# qi-charger.net
KiCad netlist of a schematic drawn in EAGLE
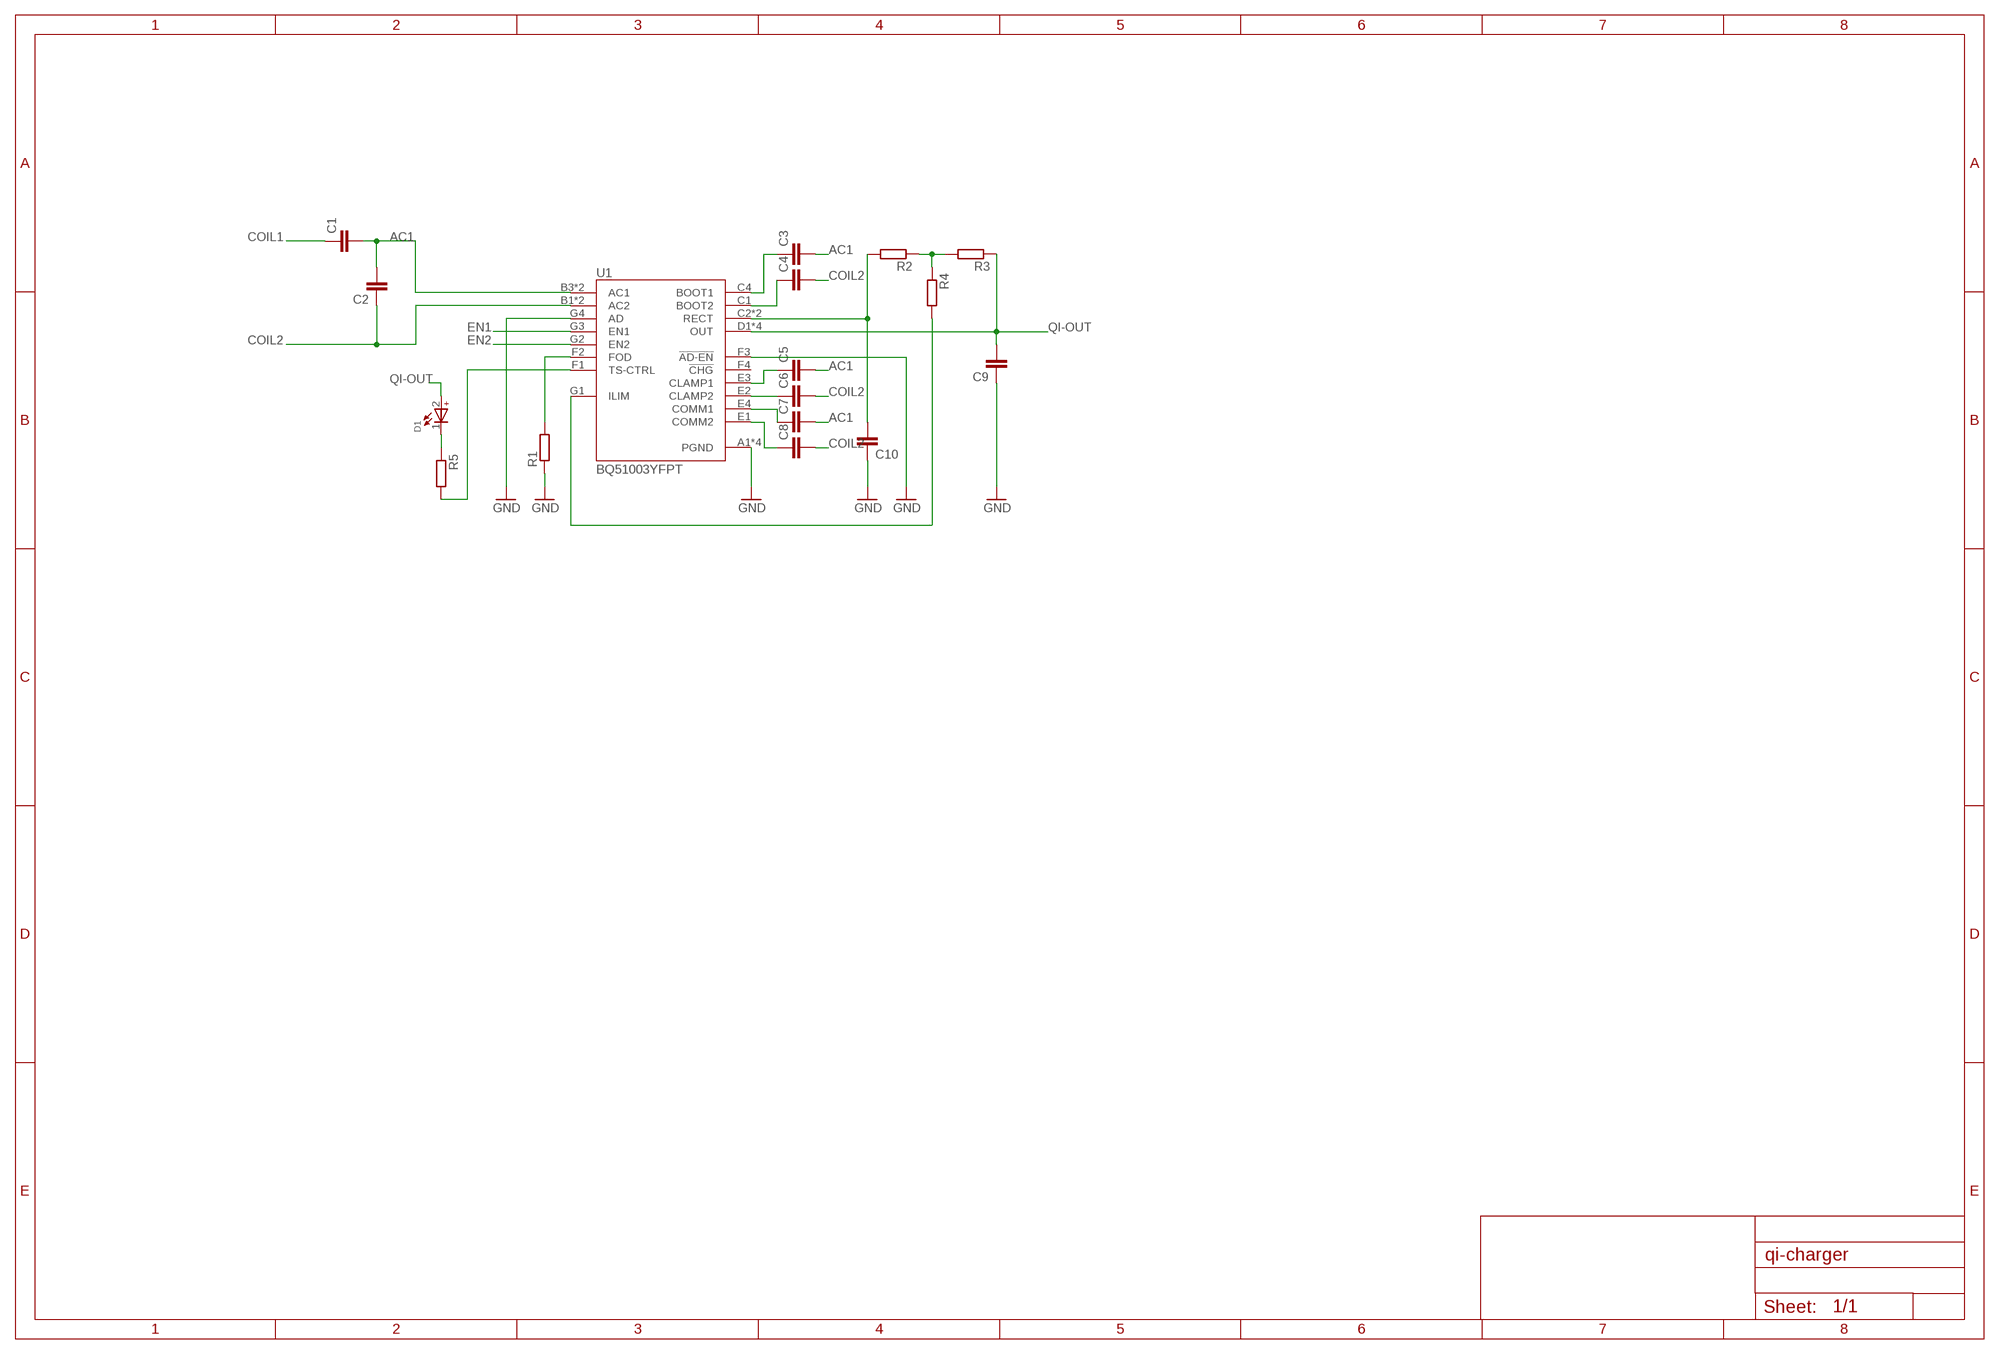
[diagram p0: schematic, sheet 1]

(export (version "E")
  (design (tool "Eeschema 10.0.6"))
  (components
    (comp (ref "C1")
      (value "C-EUC0805")
      (footprint "eagle-import:C0805")
      (libsource (lib "eagle-import") (part "C-EUC0805"))
    )
    (comp (ref "C2")
      (value "C-EUC0805")
      (footprint "eagle-import:C0805")
      (libsource (lib "eagle-import") (part "C-EUC0805"))
    )
    (comp (ref "C3")
      (value "C-EUC0805")
      (footprint "eagle-import:C0805")
      (libsource (lib "eagle-import") (part "C-EUC0805"))
    )
    (comp (ref "C4")
      (value "C-EUC0805")
      (footprint "eagle-import:C0805")
      (libsource (lib "eagle-import") (part "C-EUC0805"))
    )
    (comp (ref "C5")
      (value "C-EUC0805")
      (footprint "eagle-import:C0805")
      (libsource (lib "eagle-import") (part "C-EUC0805"))
    )
    (comp (ref "C6")
      (value "C-EUC0805")
      (footprint "eagle-import:C0805")
      (libsource (lib "eagle-import") (part "C-EUC0805"))
    )
    (comp (ref "C7")
      (value "C-EUC0805")
      (footprint "eagle-import:C0805")
      (libsource (lib "eagle-import") (part "C-EUC0805"))
    )
    (comp (ref "C8")
      (value "C-EUC0805")
      (footprint "eagle-import:C0805")
      (libsource (lib "eagle-import") (part "C-EUC0805"))
    )
    (comp (ref "C9")
      (value "C-EUC0805")
      (footprint "eagle-import:C0805")
      (libsource (lib "eagle-import") (part "C-EUC0805"))
    )
    (comp (ref "C10")
      (value "C-EUC0805")
      (footprint "eagle-import:C0805")
      (libsource (lib "eagle-import") (part "C-EUC0805"))
    )
    (comp (ref "D1")
      (value "WL-SMCW_0603_150060AS75000")
      (footprint "eagle-import:WL-SMCW_0603")
      (libsource (lib "eagle-import") (part "WL-SMCW_0603_150060AS75000"))
    )
    (comp (ref "R1")
      (value "R-EU_M0805")
      (footprint "eagle-import:M0805")
      (libsource (lib "eagle-import") (part "R-EU_M0805"))
    )
    (comp (ref "R2")
      (value "R-EU_M0805")
      (footprint "eagle-import:M0805")
      (libsource (lib "eagle-import") (part "R-EU_M0805"))
    )
    (comp (ref "R3")
      (value "R-EU_M0805")
      (footprint "eagle-import:M0805")
      (libsource (lib "eagle-import") (part "R-EU_M0805"))
    )
    (comp (ref "R4")
      (value "R-EU_M0805")
      (footprint "eagle-import:M0805")
      (libsource (lib "eagle-import") (part "R-EU_M0805"))
    )
    (comp (ref "R5")
      (value "R-EU_M0805")
      (footprint "eagle-import:M0805")
      (libsource (lib "eagle-import") (part "R-EU_M0805"))
    )
    (comp (ref "U1")
      (value "BQ51003YFPT")
      (footprint "eagle-import:BGA28N40P7X4_300X188X50N")
      (fields (field (name "MF") "Texas Instruments"))
      (libsource (lib "eagle-import") (part "BQ51003YFPT"))
    )
  )
  (nets
    (net (code "1") (name "/AC1") (class "Default")
      (node (ref "C1") (pin "2") (pinfunction "2_2") (pintype "passive"))
      (node (ref "C2") (pin "2") (pinfunction "2_2") (pintype "passive"))
      (node (ref "C3") (pin "2") (pinfunction "2_2") (pintype "passive"))
      (node (ref "C5") (pin "2") (pinfunction "2_2") (pintype "passive"))
      (node (ref "C7") (pin "2") (pinfunction "2_2") (pintype "passive"))
      (node (ref "U1") (pin "B3") (pinfunction "AC1_B3") (pintype "input"))
      (node (ref "U1") (pin "B4") (pinfunction "AC1_B4") (pintype "input"))
    )
    (net (code "2") (name "/COIL1") (class "Default")
      (node (ref "C1") (pin "1") (pinfunction "1_1") (pintype "passive"))
    )
    (net (code "3") (name "/COIL2") (class "Default")
      (node (ref "C2") (pin "1") (pinfunction "1_1") (pintype "passive"))
      (node (ref "C4") (pin "2") (pinfunction "2_2") (pintype "passive"))
      (node (ref "C6") (pin "2") (pinfunction "2_2") (pintype "passive"))
      (node (ref "C8") (pin "2") (pinfunction "2_2") (pintype "passive"))
      (node (ref "U1") (pin "B1") (pinfunction "AC2_B1") (pintype "input"))
      (node (ref "U1") (pin "B2") (pinfunction "AC2_B2") (pintype "input"))
    )
    (net (code "4") (name "/EN1") (class "Default")
      (node (ref "U1") (pin "G3") (pinfunction "EN1_G3") (pintype "input"))
    )
    (net (code "5") (name "/EN2") (class "Default")
      (node (ref "U1") (pin "G2") (pinfunction "EN2_G2") (pintype "input"))
    )
    (net (code "6") (name "/QI-OUT") (class "Default")
      (node (ref "C9") (pin "2") (pinfunction "2_2") (pintype "passive"))
      (node (ref "D1") (pin "2") (pinfunction "+_2") (pintype "passive"))
      (node (ref "R3") (pin "1") (pinfunction "1_1") (pintype "passive"))
      (node (ref "U1") (pin "D1") (pinfunction "OUT_D1") (pintype "output"))
      (node (ref "U1") (pin "D2") (pinfunction "OUT_D2") (pintype "output"))
      (node (ref "U1") (pin "D3") (pinfunction "OUT_D3") (pintype "output"))
      (node (ref "U1") (pin "D4") (pinfunction "OUT_D4") (pintype "output"))
    )
    (net (code "7") (name "GND") (class "Default")
      (node (ref "C10") (pin "1") (pinfunction "1_1") (pintype "passive"))
      (node (ref "C9") (pin "1") (pinfunction "1_1") (pintype "passive"))
      (node (ref "R1") (pin "1") (pinfunction "1_1") (pintype "passive"))
      (node (ref "U1") (pin "A1") (pinfunction "PGND_A1") (pintype "power_in"))
      (node (ref "U1") (pin "A2") (pinfunction "PGND_A2") (pintype "power_in"))
      (node (ref "U1") (pin "A3") (pinfunction "PGND_A3") (pintype "power_in"))
      (node (ref "U1") (pin "A4") (pinfunction "PGND_A4") (pintype "power_in"))
      (node (ref "U1") (pin "F3") (pinfunction "~{AD-EN}_F3") (pintype "output"))
      (node (ref "U1") (pin "G4") (pinfunction "AD_G4") (pintype "input"))
    )
    (net (code "8") (name "Net-(C10-Pad2)") (class "Default")
      (node (ref "C10") (pin "2") (pinfunction "2_2") (pintype "passive"))
      (node (ref "R2") (pin "2") (pinfunction "2_2") (pintype "passive"))
      (node (ref "U1") (pin "C2") (pinfunction "RECT_C2") (pintype "output"))
      (node (ref "U1") (pin "C3") (pinfunction "RECT_C3") (pintype "output"))
    )
    (net (code "9") (name "Net-(D1--)") (class "Default")
      (node (ref "D1") (pin "1") (pinfunction "-_1") (pintype "passive"))
      (node (ref "R5") (pin "1") (pinfunction "1_1") (pintype "passive"))
    )
    (net (code "10") (name "Net-(R2-Pad1)") (class "Default")
      (node (ref "R2") (pin "1") (pinfunction "1_1") (pintype "passive"))
      (node (ref "R3") (pin "2") (pinfunction "2_2") (pintype "passive"))
      (node (ref "R4") (pin "1") (pinfunction "1_1") (pintype "passive"))
    )
    (net (code "11") (name "Net-(U1-BOOT1)") (class "Default")
      (node (ref "C3") (pin "1") (pinfunction "1_1") (pintype "passive"))
      (node (ref "U1") (pin "C4") (pinfunction "BOOT1_C4") (pintype "output"))
    )
    (net (code "12") (name "Net-(U1-BOOT2)") (class "Default")
      (node (ref "C4") (pin "1") (pinfunction "1_1") (pintype "passive"))
      (node (ref "U1") (pin "C1") (pinfunction "BOOT2_C1") (pintype "output"))
    )
    (net (code "13") (name "Net-(U1-CLAMP1)") (class "Default")
      (node (ref "C5") (pin "1") (pinfunction "1_1") (pintype "passive"))
      (node (ref "U1") (pin "E3") (pinfunction "CLAMP1_E3") (pintype "output"))
    )
    (net (code "14") (name "Net-(U1-CLAMP2)") (class "Default")
      (node (ref "C6") (pin "1") (pinfunction "1_1") (pintype "passive"))
      (node (ref "U1") (pin "E2") (pinfunction "CLAMP2_E2") (pintype "output"))
    )
    (net (code "15") (name "Net-(U1-COMM1)") (class "Default")
      (node (ref "C7") (pin "1") (pinfunction "1_1") (pintype "passive"))
      (node (ref "U1") (pin "E4") (pinfunction "COMM1_E4") (pintype "output"))
    )
    (net (code "16") (name "Net-(U1-COMM2)") (class "Default")
      (node (ref "C8") (pin "1") (pinfunction "1_1") (pintype "passive"))
      (node (ref "U1") (pin "E1") (pinfunction "COMM2_E1") (pintype "output"))
    )
    (net (code "17") (name "Net-(U1-FOD)") (class "Default")
      (node (ref "R1") (pin "2") (pinfunction "2_2") (pintype "passive"))
      (node (ref "U1") (pin "F2") (pinfunction "FOD_F2") (pintype "input"))
    )
    (net (code "18") (name "Net-(U1-ILIM)") (class "Default")
      (node (ref "R4") (pin "2") (pinfunction "2_2") (pintype "passive"))
      (node (ref "U1") (pin "G1") (pinfunction "ILIM_G1") (pintype "bidirectional"))
    )
    (net (code "19") (name "Net-(U1-TS-CTRL)") (class "Default")
      (node (ref "R5") (pin "2") (pinfunction "2_2") (pintype "passive"))
      (node (ref "U1") (pin "F1") (pinfunction "TS-CTRL_F1") (pintype "input"))
    )
    (net (code "20") (name "unconnected-(U1-~{CHG}-PadF4)") (class "Default")
      (node (ref "U1") (pin "F4") (pinfunction "~{CHG}_F4") (pintype "output"))
    )
  )
)
